# pic32.net
KiCad netlist of a schematic drawn in EAGLE
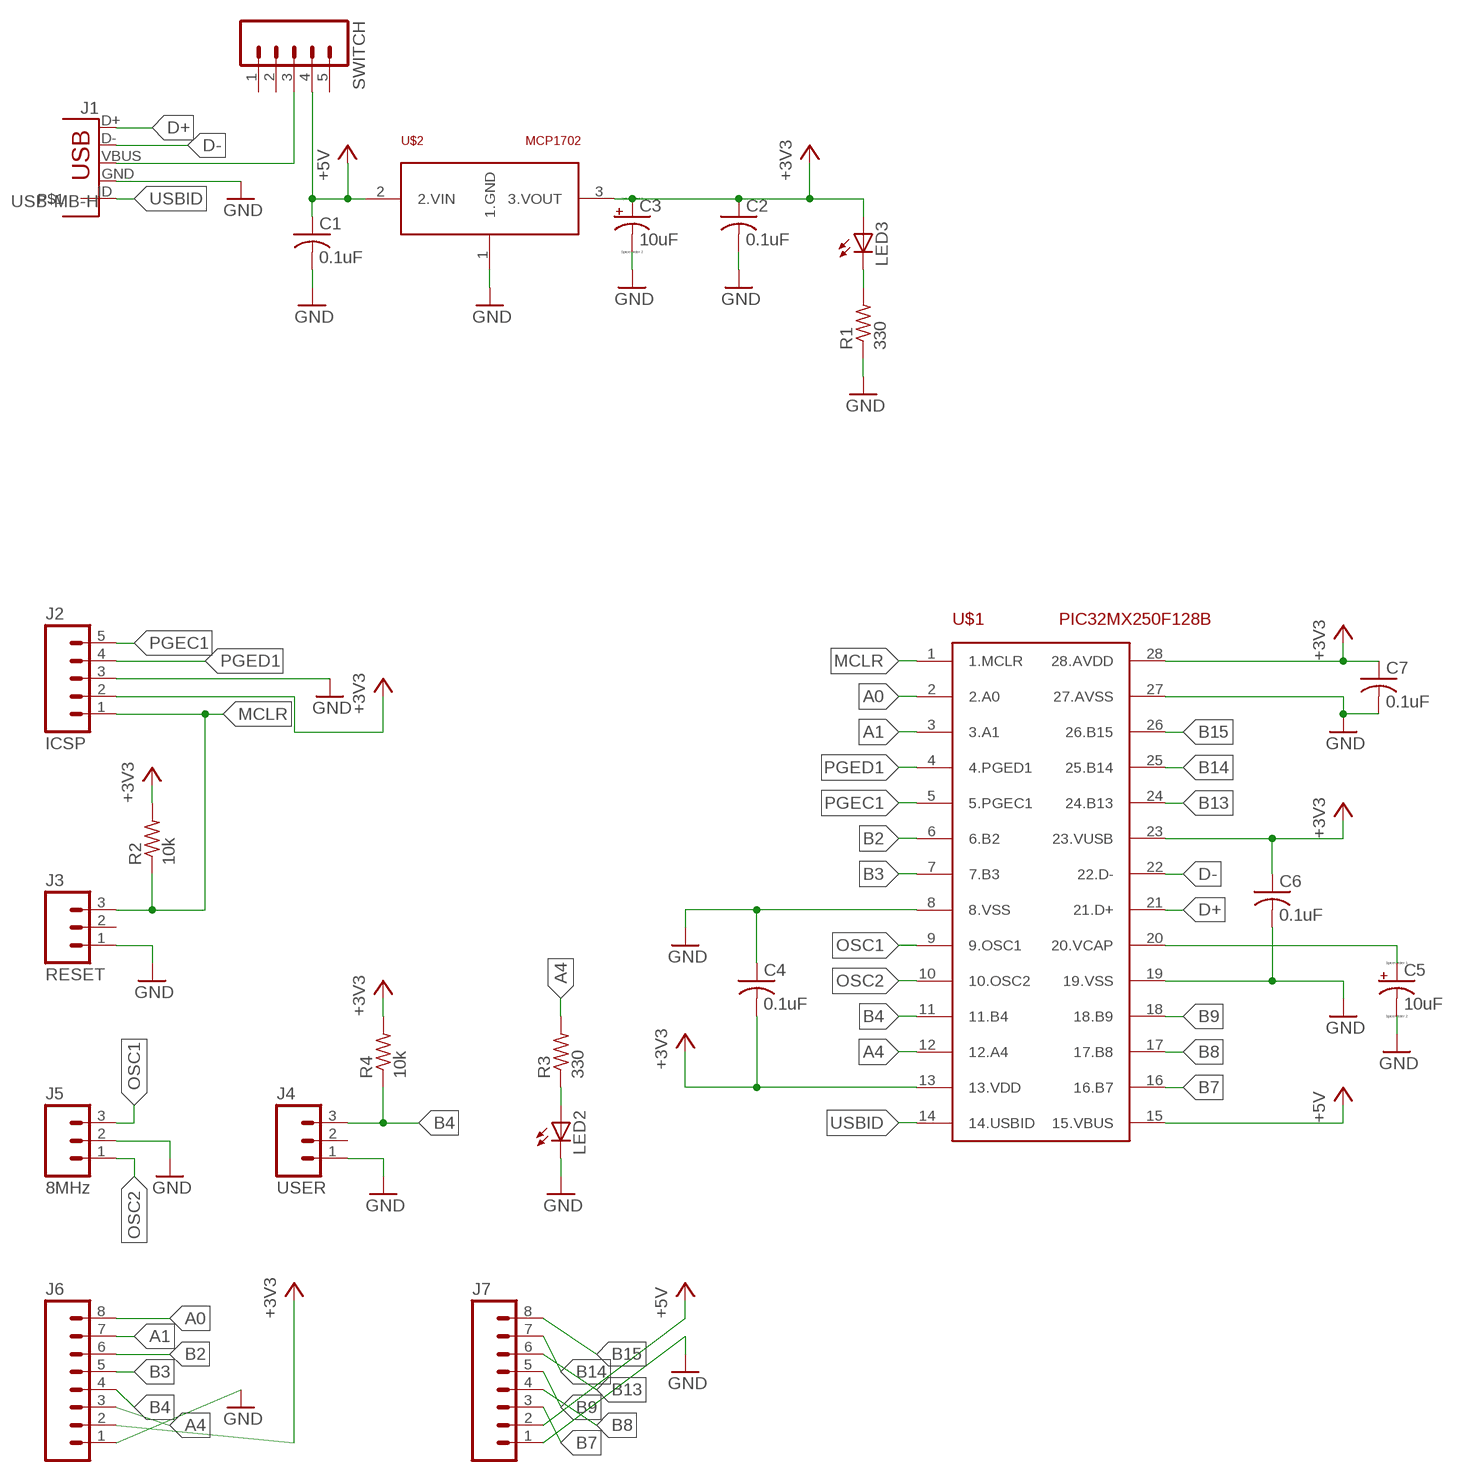
[diagram p0: schematic, sheet 1]

(export (version "E")
  (design (tool "Eeschema 10.0.6"))
  (components
    (comp (ref "C1")
      (value "0.1uF")
      (footprint "eagle-import:C025-024X044")
      (libsource (lib "eagle-import") (part "C-US025-024X044"))
    )
    (comp (ref "C2")
      (value "0.1uF")
      (footprint "eagle-import:C025-024X044")
      (libsource (lib "eagle-import") (part "C-US025-024X044"))
    )
    (comp (ref "C3")
      (value "10uF")
      (footprint "eagle-import:E1,8-4")
      (libsource (lib "eagle-import") (part "CPOL-USE1.8-4"))
    )
    (comp (ref "C4")
      (value "0.1uF")
      (footprint "eagle-import:C025-024X044")
      (libsource (lib "eagle-import") (part "C-US025-024X044"))
    )
    (comp (ref "C5")
      (value "10uF")
      (footprint "eagle-import:E1,8-4")
      (libsource (lib "eagle-import") (part "CPOL-USE1.8-4"))
    )
    (comp (ref "C6")
      (value "0.1uF")
      (footprint "eagle-import:C025-024X044")
      (libsource (lib "eagle-import") (part "C-US025-024X044"))
    )
    (comp (ref "C7")
      (value "0.1uF")
      (footprint "eagle-import:C025-024X044")
      (libsource (lib "eagle-import") (part "C-US025-024X044"))
    )
    (comp (ref "J1")
      (value "USB-MB-H")
      (footprint "eagle-import:USB-MB-H")
      (libsource (lib "eagle-import") (part "USB-MB-H"))
    )
    (comp (ref "J2")
      (value "ICSP")
      (footprint "eagle-import:1X05")
      (libsource (lib "eagle-import") (part "M05PTH"))
    )
    (comp (ref "J3")
      (value "RESET")
      (footprint "eagle-import:1X03")
      (libsource (lib "eagle-import") (part "M03PTH"))
    )
    (comp (ref "J4")
      (value "USER")
      (footprint "eagle-import:1X03")
      (libsource (lib "eagle-import") (part "M03PTH"))
    )
    (comp (ref "J5")
      (value "8MHz")
      (footprint "eagle-import:1X03")
      (libsource (lib "eagle-import") (part "M03PTH"))
    )
    (comp (ref "J6")
      (value "M08")
      (footprint "eagle-import:1X08_ROUND")
      (libsource (lib "eagle-import") (part "M08"))
    )
    (comp (ref "J7")
      (value "M08")
      (footprint "eagle-import:1X08_ROUND")
      (libsource (lib "eagle-import") (part "M08"))
    )
    (comp (ref "LED2")
      (value "LED3MM")
      (footprint "eagle-import:LED3MM")
      (libsource (lib "eagle-import") (part "LED3MM"))
    )
    (comp (ref "LED3")
      (value "LED3MM")
      (footprint "eagle-import:LED3MM")
      (libsource (lib "eagle-import") (part "LED3MM"))
    )
    (comp (ref "R1")
      (value "330")
      (footprint "eagle-import:0207_10")
      (libsource (lib "eagle-import") (part "R-US_0207/10"))
    )
    (comp (ref "R2")
      (value "10k")
      (footprint "eagle-import:0207_10")
      (libsource (lib "eagle-import") (part "R-US_0207/10"))
    )
    (comp (ref "R3")
      (value "330")
      (footprint "eagle-import:0207_10")
      (libsource (lib "eagle-import") (part "R-US_0207/10"))
    )
    (comp (ref "R4")
      (value "10k")
      (footprint "eagle-import:0207_10")
      (libsource (lib "eagle-import") (part "R-US_0207/10"))
    )
    (comp (ref "SWITCH")
      (value "M05PTH")
      (footprint "eagle-import:1X05")
      (libsource (lib "eagle-import") (part "M05PTH"))
    )
    (comp (ref "U$1")
      (value "PIC32MX250F128B")
      (footprint "eagle-import:DIL28-3")
      (libsource (lib "eagle-import") (part "PIC32MX250F128B"))
    )
    (comp (ref "U$2")
      (value "MCP1702")
      (footprint "eagle-import:TO92")
      (libsource (lib "eagle-import") (part "MCP1702"))
    )
  )
  (nets
    (net (code "1") (name "+3V3") (class "Default")
      (node (ref "C2") (pin "1") (pinfunction "1_1") (pintype "passive"))
      (node (ref "C3") (pin "+") (pinfunction "+_+") (pintype "passive"))
      (node (ref "C4") (pin "2") (pinfunction "2_2") (pintype "passive"))
      (node (ref "C6") (pin "1") (pinfunction "1_1") (pintype "passive"))
      (node (ref "C7") (pin "1") (pinfunction "1_1") (pintype "passive"))
      (node (ref "J2") (pin "2") (pinfunction "2_2") (pintype "passive"))
      (node (ref "J6") (pin "2") (pinfunction "2_2") (pintype "passive"))
      (node (ref "LED3") (pin "A") (pinfunction "A_A") (pintype "passive"))
      (node (ref "R2") (pin "2") (pinfunction "2_2") (pintype "passive"))
      (node (ref "R4") (pin "2") (pinfunction "2_2") (pintype "passive"))
      (node (ref "U$1") (pin "13") (pinfunction "13.VDD_13") (pintype "bidirectional"))
      (node (ref "U$1") (pin "23") (pinfunction "23.VUSB_23") (pintype "bidirectional"))
      (node (ref "U$1") (pin "28") (pinfunction "28.AVDD_28") (pintype "bidirectional"))
      (node (ref "U$2") (pin "3") (pinfunction "3.VOUT_3") (pintype "bidirectional"))
    )
    (net (code "2") (name "+5V") (class "Default")
      (node (ref "C1") (pin "1") (pinfunction "1_1") (pintype "passive"))
      (node (ref "J7") (pin "2") (pinfunction "2_2") (pintype "passive"))
      (node (ref "SWITCH") (pin "4") (pinfunction "4_4") (pintype "passive"))
      (node (ref "U$1") (pin "15") (pinfunction "15.VBUS_15") (pintype "bidirectional"))
      (node (ref "U$2") (pin "2") (pinfunction "2.VIN_2") (pintype "bidirectional"))
    )
    (net (code "3") (name "A0") (class "Default")
      (node (ref "J6") (pin "8") (pinfunction "8_8") (pintype "passive"))
      (node (ref "U$1") (pin "2") (pinfunction "2.A0_2") (pintype "bidirectional"))
    )
    (net (code "4") (name "A1") (class "Default")
      (node (ref "J6") (pin "7") (pinfunction "7_7") (pintype "passive"))
      (node (ref "U$1") (pin "3") (pinfunction "3.A1_3") (pintype "bidirectional"))
    )
    (net (code "5") (name "A4") (class "Default")
      (node (ref "J6") (pin "3") (pinfunction "3_3") (pintype "passive"))
      (node (ref "R3") (pin "2") (pinfunction "2_2") (pintype "passive"))
      (node (ref "U$1") (pin "12") (pinfunction "12.A4_12") (pintype "bidirectional"))
    )
    (net (code "6") (name "B2") (class "Default")
      (node (ref "J6") (pin "6") (pinfunction "6_6") (pintype "passive"))
      (node (ref "U$1") (pin "6") (pinfunction "6.B2_6") (pintype "bidirectional"))
    )
    (net (code "7") (name "B3") (class "Default")
      (node (ref "J6") (pin "5") (pinfunction "5_5") (pintype "passive"))
      (node (ref "U$1") (pin "7") (pinfunction "7.B3_7") (pintype "bidirectional"))
    )
    (net (code "8") (name "B4") (class "Default")
      (node (ref "J4") (pin "3") (pinfunction "3_3") (pintype "passive"))
      (node (ref "J6") (pin "4") (pinfunction "4_4") (pintype "passive"))
      (node (ref "R4") (pin "1") (pinfunction "1_1") (pintype "passive"))
      (node (ref "U$1") (pin "11") (pinfunction "11.B4_11") (pintype "bidirectional"))
    )
    (net (code "9") (name "B7") (class "Default")
      (node (ref "J7") (pin "3") (pinfunction "3_3") (pintype "passive"))
      (node (ref "U$1") (pin "16") (pinfunction "16.B7_16") (pintype "bidirectional"))
    )
    (net (code "10") (name "B8") (class "Default")
      (node (ref "J7") (pin "4") (pinfunction "4_4") (pintype "passive"))
      (node (ref "U$1") (pin "17") (pinfunction "17.B8_17") (pintype "bidirectional"))
    )
    (net (code "11") (name "B9") (class "Default")
      (node (ref "J7") (pin "5") (pinfunction "5_5") (pintype "passive"))
      (node (ref "U$1") (pin "18") (pinfunction "18.B9_18") (pintype "bidirectional"))
    )
    (net (code "12") (name "B13") (class "Default")
      (node (ref "J7") (pin "6") (pinfunction "6_6") (pintype "passive"))
      (node (ref "U$1") (pin "24") (pinfunction "24.B13_24") (pintype "bidirectional"))
    )
    (net (code "13") (name "B14") (class "Default")
      (node (ref "J7") (pin "7") (pinfunction "7_7") (pintype "passive"))
      (node (ref "U$1") (pin "25") (pinfunction "25.B14_25") (pintype "bidirectional"))
    )
    (net (code "14") (name "B15") (class "Default")
      (node (ref "J7") (pin "8") (pinfunction "8_8") (pintype "passive"))
      (node (ref "U$1") (pin "26") (pinfunction "26.B15_26") (pintype "bidirectional"))
    )
    (net (code "15") (name "D+") (class "Default")
      (node (ref "J1") (pin "D+") (pinfunction "D+_D+") (pintype "bidirectional"))
      (node (ref "U$1") (pin "21") (pinfunction "21.D+_21") (pintype "bidirectional"))
    )
    (net (code "16") (name "D-") (class "Default")
      (node (ref "J1") (pin "D-") (pinfunction "D-_D-") (pintype "bidirectional"))
      (node (ref "U$1") (pin "22") (pinfunction "22.D-_22") (pintype "bidirectional"))
    )
    (net (code "17") (name "GND") (class "Default")
      (node (ref "C1") (pin "2") (pinfunction "2_2") (pintype "passive"))
      (node (ref "C2") (pin "2") (pinfunction "2_2") (pintype "passive"))
      (node (ref "C3") (pin "-") (pinfunction "-_-") (pintype "passive"))
      (node (ref "C4") (pin "1") (pinfunction "1_1") (pintype "passive"))
      (node (ref "C5") (pin "-") (pinfunction "-_-") (pintype "passive"))
      (node (ref "C6") (pin "2") (pinfunction "2_2") (pintype "passive"))
      (node (ref "C7") (pin "2") (pinfunction "2_2") (pintype "passive"))
      (node (ref "J1") (pin "GND") (pinfunction "GND_GND") (pintype "bidirectional"))
      (node (ref "J2") (pin "3") (pinfunction "3_3") (pintype "passive"))
      (node (ref "J3") (pin "1") (pinfunction "1_1") (pintype "passive"))
      (node (ref "J4") (pin "1") (pinfunction "1_1") (pintype "passive"))
      (node (ref "J5") (pin "2") (pinfunction "2_2") (pintype "passive"))
      (node (ref "J6") (pin "1") (pinfunction "1_1") (pintype "passive"))
      (node (ref "J7") (pin "1") (pinfunction "1_1") (pintype "passive"))
      (node (ref "LED2") (pin "K") (pinfunction "C_K") (pintype "passive"))
      (node (ref "R1") (pin "1") (pinfunction "1_1") (pintype "passive"))
      (node (ref "U$1") (pin "19") (pinfunction "19.VSS_19") (pintype "bidirectional"))
      (node (ref "U$1") (pin "27") (pinfunction "27.AVSS_27") (pintype "bidirectional"))
      (node (ref "U$1") (pin "8") (pinfunction "8.VSS_8") (pintype "bidirectional"))
      (node (ref "U$2") (pin "1") (pinfunction "1.GND_1") (pintype "bidirectional"))
    )
    (net (code "18") (name "MCLR") (class "Default")
      (node (ref "J2") (pin "1") (pinfunction "1_1") (pintype "passive"))
      (node (ref "J3") (pin "3") (pinfunction "3_3") (pintype "passive"))
      (node (ref "R2") (pin "1") (pinfunction "1_1") (pintype "passive"))
      (node (ref "U$1") (pin "1") (pinfunction "1.MCLR_1") (pintype "bidirectional"))
    )
    (net (code "19") (name "Net-(J1-PadVBUS)") (class "Default")
      (node (ref "J1") (pin "VBUS") (pinfunction "VBUS_VBUS") (pintype "bidirectional"))
      (node (ref "SWITCH") (pin "3") (pinfunction "3_3") (pintype "passive"))
    )
    (net (code "20") (name "Net-(LED2-PadA)") (class "Default")
      (node (ref "LED2") (pin "A") (pinfunction "A_A") (pintype "passive"))
      (node (ref "R3") (pin "1") (pinfunction "1_1") (pintype "passive"))
    )
    (net (code "21") (name "Net-(LED3-C)") (class "Default")
      (node (ref "LED3") (pin "K") (pinfunction "C_K") (pintype "passive"))
      (node (ref "R1") (pin "2") (pinfunction "2_2") (pintype "passive"))
    )
    (net (code "22") (name "Net-(U$1-20.VCAP)") (class "Default")
      (node (ref "C5") (pin "+") (pinfunction "+_+") (pintype "passive"))
      (node (ref "U$1") (pin "20") (pinfunction "20.VCAP_20") (pintype "bidirectional"))
    )
    (net (code "23") (name "OSC1") (class "Default")
      (node (ref "J5") (pin "3") (pinfunction "3_3") (pintype "passive"))
      (node (ref "U$1") (pin "9") (pinfunction "9.OSC1_9") (pintype "bidirectional"))
    )
    (net (code "24") (name "OSC2") (class "Default")
      (node (ref "J5") (pin "1") (pinfunction "1_1") (pintype "passive"))
      (node (ref "U$1") (pin "10") (pinfunction "10.OSC2_10") (pintype "bidirectional"))
    )
    (net (code "25") (name "PGEC1") (class "Default")
      (node (ref "J2") (pin "5") (pinfunction "5_5") (pintype "passive"))
      (node (ref "U$1") (pin "5") (pinfunction "5.PGEC1_5") (pintype "bidirectional"))
    )
    (net (code "26") (name "PGED1") (class "Default")
      (node (ref "J2") (pin "4") (pinfunction "4_4") (pintype "passive"))
      (node (ref "U$1") (pin "4") (pinfunction "4.PGED1_4") (pintype "bidirectional"))
    )
    (net (code "27") (name "USBID") (class "Default")
      (node (ref "J1") (pin "ID") (pinfunction "P$1_ID") (pintype "bidirectional"))
      (node (ref "U$1") (pin "14") (pinfunction "14.USBID_14") (pintype "bidirectional"))
    )
    (net (code "28") (name "unconnected-(J3-Pad2)") (class "Default")
      (node (ref "J3") (pin "2") (pinfunction "2_2") (pintype "passive"))
    )
    (net (code "29") (name "unconnected-(J4-Pad2)") (class "Default")
      (node (ref "J4") (pin "2") (pinfunction "2_2") (pintype "passive"))
    )
    (net (code "30") (name "unconnected-(SWITCH-Pad1)") (class "Default")
      (node (ref "SWITCH") (pin "1") (pinfunction "1_1") (pintype "passive"))
    )
    (net (code "31") (name "unconnected-(SWITCH-Pad2)") (class "Default")
      (node (ref "SWITCH") (pin "2") (pinfunction "2_2") (pintype "passive"))
    )
    (net (code "32") (name "unconnected-(SWITCH-Pad5)") (class "Default")
      (node (ref "SWITCH") (pin "5") (pinfunction "5_5") (pintype "passive"))
    )
  )
)
